# Microduino-Core_BLE.net
KiCad netlist of a schematic drawn in EAGLE
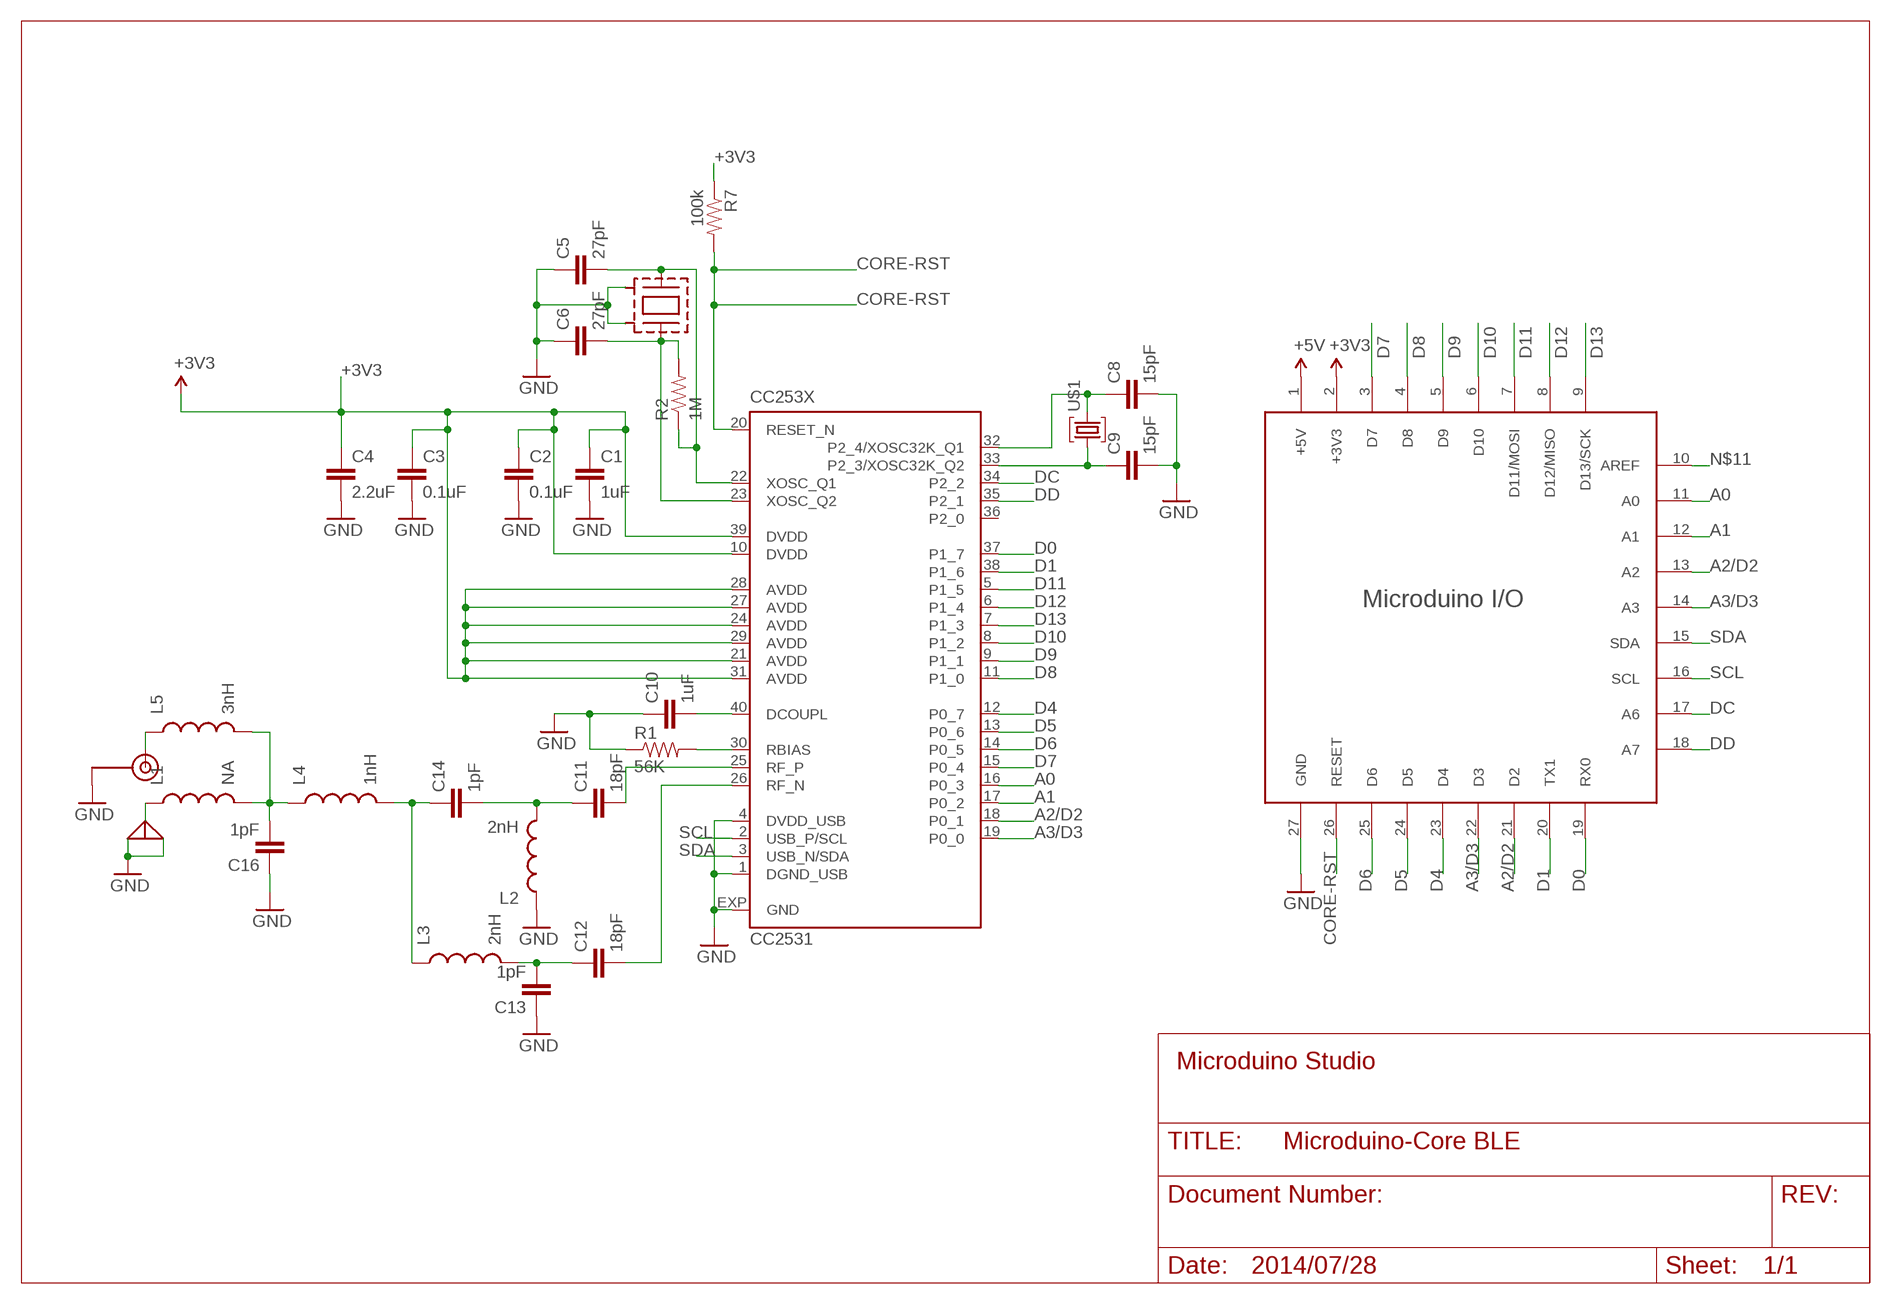
[diagram p0: schematic, sheet 1]

(export (version "E")
  (design (tool "Eeschema 10.0.6"))
  (components
    (comp (ref "C1")
      (value "1uF")
      (footprint "eagle-import:0603-CAP")
      (libsource (lib "eagle-import") (part "CAP0603-CAP"))
    )
    (comp (ref "C2")
      (value "0.1uF")
      (footprint "eagle-import:0402-CAP")
      (libsource (lib "eagle-import") (part "CAP0402-CAP"))
    )
    (comp (ref "C3")
      (value "0.1uF")
      (footprint "eagle-import:0402-CAP")
      (libsource (lib "eagle-import") (part "CAP0402-CAP"))
    )
    (comp (ref "C4")
      (value "2.2uF")
      (footprint "eagle-import:0402-CAP")
      (libsource (lib "eagle-import") (part "CAP0402-CAP"))
    )
    (comp (ref "C5")
      (value "27pF")
      (footprint "eagle-import:0402-CAP")
      (libsource (lib "eagle-import") (part "CAP0402-CAP"))
    )
    (comp (ref "C6")
      (value "27pF")
      (footprint "eagle-import:0402-CAP")
      (libsource (lib "eagle-import") (part "CAP0402-CAP"))
    )
    (comp (ref "C8")
      (value "15pF")
      (footprint "eagle-import:0402-CAP")
      (libsource (lib "eagle-import") (part "CAP0402-CAP"))
    )
    (comp (ref "C9")
      (value "15pF")
      (footprint "eagle-import:0402-CAP")
      (libsource (lib "eagle-import") (part "CAP0402-CAP"))
    )
    (comp (ref "C10")
      (value "1uF")
      (footprint "eagle-import:0603-CAP")
      (libsource (lib "eagle-import") (part "CAP0603-CAP"))
    )
    (comp (ref "C11")
      (value "18pF")
      (footprint "eagle-import:0402-CAP")
      (libsource (lib "eagle-import") (part "CAP0402-CAP"))
    )
    (comp (ref "C12")
      (value "18pF")
      (footprint "eagle-import:0402-CAP")
      (libsource (lib "eagle-import") (part "CAP0402-CAP"))
    )
    (comp (ref "C13")
      (value "1pF")
      (footprint "eagle-import:0402-CAP")
      (libsource (lib "eagle-import") (part "CAP0402-CAP"))
    )
    (comp (ref "C14")
      (value "1pF")
      (footprint "eagle-import:0402-CAP")
      (libsource (lib "eagle-import") (part "CAP0402-CAP"))
    )
    (comp (ref "C16")
      (value "1pF")
      (footprint "eagle-import:0402-CAP")
      (libsource (lib "eagle-import") (part "CAP0402-CAP"))
    )
    (comp (ref "CC253X")
      (value "CC2531")
      (footprint "eagle-import:RHA_S-PVQFN-N40")
      (fields (field (name "MPN") "CC2531F256RHAT"))
      (libsource (lib "eagle-import") (part "CC2531"))
    )
    (comp (ref "CRYS.1")
      (value "CRYSTAL-SMD")
      (footprint "eagle-import:CRYSTAL-SMD-3225")
      (libsource (lib "eagle-import") (part "CRYSTAL-SMD"))
    )
    (comp (ref "L1")
      (value "NA")
      (footprint "eagle-import:C0402")
      (libsource (lib "eagle-import") (part "INDUCTOR0402"))
    )
    (comp (ref "L2")
      (value "2nH")
      (footprint "eagle-import:C0402")
      (libsource (lib "eagle-import") (part "INDUCTOR0402"))
    )
    (comp (ref "L3")
      (value "2nH")
      (footprint "eagle-import:C0402")
      (libsource (lib "eagle-import") (part "INDUCTOR0402"))
    )
    (comp (ref "L4")
      (value "1nH")
      (footprint "eagle-import:C0402")
      (libsource (lib "eagle-import") (part "INDUCTOR0402"))
    )
    (comp (ref "L5")
      (value "3nH")
      (footprint "eagle-import:C0402")
      (libsource (lib "eagle-import") (part "INDUCTOR0402"))
    )
    (comp (ref "R1")
      (value "56K")
      (footprint "eagle-import:0402-RES")
      (libsource (lib "eagle-import") (part "RESISTOR0402-RES"))
    )
    (comp (ref "R2")
      (value "1M")
      (footprint "eagle-import:0402-RES")
      (libsource (lib "eagle-import") (part "RESISTOR0402-RES"))
    )
    (comp (ref "R7")
      (value "100k")
      (footprint "eagle-import:0402-RES")
      (libsource (lib "eagle-import") (part "RESISTOR0402-RES"))
    )
    (comp (ref "U$1")
      (value "32.768-3215")
      (footprint "eagle-import:3215-2PIN")
      (libsource (lib "eagle-import") (part "32.768-3215"))
    )
    (comp (ref "U$2")
      (value "ANT-2.4G")
      (footprint "eagle-import:ANT2.4G")
      (libsource (lib "eagle-import") (part "ANT-2.4G"))
    )
    (comp (ref "U$3")
      (value "ANT-IPEX")
      (footprint "eagle-import:IPEX")
      (libsource (lib "eagle-import") (part "ANT-IPEX"))
    )
    (comp (ref "U$7")
      (value "MICRDUINO-PINNORMAL")
      (footprint "eagle-import:27UPIN-NORMAL")
      (libsource (lib "eagle-import") (part "MICRDUINO-PINNORMAL"))
    )
  )
  (nets
    (net (code "1") (name "+3V3") (class "Default")
      (node (ref "C1") (pin "1") (pinfunction "1_1") (pintype "passive"))
      (node (ref "C2") (pin "1") (pinfunction "1_1") (pintype "passive"))
      (node (ref "C3") (pin "1") (pinfunction "1_1") (pintype "passive"))
      (node (ref "C4") (pin "1") (pinfunction "1_1") (pintype "passive"))
      (node (ref "CC253X") (pin "10") (pinfunction "DVDD_10") (pintype "power_in"))
      (node (ref "CC253X") (pin "21") (pinfunction "AVDD_21") (pintype "power_in"))
      (node (ref "CC253X") (pin "24") (pinfunction "AVDD_24") (pintype "power_in"))
      (node (ref "CC253X") (pin "27") (pinfunction "AVDD_27") (pintype "power_in"))
      (node (ref "CC253X") (pin "28") (pinfunction "AVDD_28") (pintype "power_in"))
      (node (ref "CC253X") (pin "29") (pinfunction "AVDD_29") (pintype "power_in"))
      (node (ref "CC253X") (pin "31") (pinfunction "AVDD_31") (pintype "power_in"))
      (node (ref "CC253X") (pin "39") (pinfunction "DVDD_39") (pintype "power_in"))
      (node (ref "R7") (pin "1") (pinfunction "1_1") (pintype "passive"))
      (node (ref "U$7") (pin "2") (pinfunction "+3V3_2") (pintype "bidirectional"))
    )
    (net (code "2") (name "+5V") (class "Default")
      (node (ref "U$7") (pin "1") (pinfunction "+5V_1") (pintype "bidirectional"))
    )
    (net (code "3") (name "/A0") (class "Default")
      (node (ref "CC253X") (pin "16") (pinfunction "P0_3_16") (pintype "bidirectional"))
      (node (ref "U$7") (pin "11") (pinfunction "A0_11") (pintype "bidirectional"))
    )
    (net (code "4") (name "/A1") (class "Default")
      (node (ref "CC253X") (pin "17") (pinfunction "P0_2_17") (pintype "bidirectional"))
      (node (ref "U$7") (pin "12") (pinfunction "A1_12") (pintype "bidirectional"))
    )
    (net (code "5") (name "/A2{slash}D2") (class "Default")
      (node (ref "CC253X") (pin "18") (pinfunction "P0_1_18") (pintype "bidirectional"))
      (node (ref "U$7") (pin "13") (pinfunction "A2_13") (pintype "bidirectional"))
      (node (ref "U$7") (pin "21") (pinfunction "D2_21") (pintype "bidirectional"))
    )
    (net (code "6") (name "/A3{slash}D3") (class "Default")
      (node (ref "CC253X") (pin "19") (pinfunction "P0_0_19") (pintype "bidirectional"))
      (node (ref "U$7") (pin "14") (pinfunction "A3_14") (pintype "bidirectional"))
      (node (ref "U$7") (pin "22") (pinfunction "D3_22") (pintype "bidirectional"))
    )
    (net (code "7") (name "/CORE-RST") (class "Default")
      (node (ref "CC253X") (pin "20") (pinfunction "RESET_N_20") (pintype "input"))
      (node (ref "R7") (pin "2") (pinfunction "2_2") (pintype "passive"))
      (node (ref "U$7") (pin "26") (pinfunction "RESET_26") (pintype "bidirectional"))
    )
    (net (code "8") (name "/D0") (class "Default")
      (node (ref "CC253X") (pin "37") (pinfunction "P1_7_37") (pintype "bidirectional"))
      (node (ref "U$7") (pin "19") (pinfunction "RX0_19") (pintype "bidirectional"))
    )
    (net (code "9") (name "/D1") (class "Default")
      (node (ref "CC253X") (pin "38") (pinfunction "P1_6_38") (pintype "bidirectional"))
      (node (ref "U$7") (pin "20") (pinfunction "TX1_20") (pintype "bidirectional"))
    )
    (net (code "10") (name "/D4") (class "Default")
      (node (ref "CC253X") (pin "12") (pinfunction "P0_7_12") (pintype "bidirectional"))
      (node (ref "U$7") (pin "23") (pinfunction "D4_23") (pintype "bidirectional"))
    )
    (net (code "11") (name "/D5") (class "Default")
      (node (ref "CC253X") (pin "13") (pinfunction "P0_6_13") (pintype "bidirectional"))
      (node (ref "U$7") (pin "24") (pinfunction "D5_24") (pintype "bidirectional"))
    )
    (net (code "12") (name "/D6") (class "Default")
      (node (ref "CC253X") (pin "14") (pinfunction "P0_5_14") (pintype "bidirectional"))
      (node (ref "U$7") (pin "25") (pinfunction "D6_25") (pintype "bidirectional"))
    )
    (net (code "13") (name "/D7") (class "Default")
      (node (ref "CC253X") (pin "15") (pinfunction "P0_4_15") (pintype "bidirectional"))
      (node (ref "U$7") (pin "3") (pinfunction "D7_3") (pintype "bidirectional"))
    )
    (net (code "14") (name "/D8") (class "Default")
      (node (ref "CC253X") (pin "11") (pinfunction "P1_0_11") (pintype "bidirectional"))
      (node (ref "U$7") (pin "4") (pinfunction "D8_4") (pintype "bidirectional"))
    )
    (net (code "15") (name "/D9") (class "Default")
      (node (ref "CC253X") (pin "9") (pinfunction "P1_1_9") (pintype "bidirectional"))
      (node (ref "U$7") (pin "5") (pinfunction "D9_5") (pintype "bidirectional"))
    )
    (net (code "16") (name "/D10") (class "Default")
      (node (ref "CC253X") (pin "8") (pinfunction "P1_2_8") (pintype "bidirectional"))
      (node (ref "U$7") (pin "6") (pinfunction "D10_6") (pintype "bidirectional"))
    )
    (net (code "17") (name "/D11") (class "Default")
      (node (ref "CC253X") (pin "5") (pinfunction "P1_5_5") (pintype "bidirectional"))
      (node (ref "U$7") (pin "7") (pinfunction "D11/MOSI_7") (pintype "bidirectional"))
    )
    (net (code "18") (name "/D12") (class "Default")
      (node (ref "CC253X") (pin "6") (pinfunction "P1_4_6") (pintype "bidirectional"))
      (node (ref "U$7") (pin "8") (pinfunction "D12/MISO_8") (pintype "bidirectional"))
    )
    (net (code "19") (name "/D13") (class "Default")
      (node (ref "CC253X") (pin "7") (pinfunction "P1_3_7") (pintype "bidirectional"))
      (node (ref "U$7") (pin "9") (pinfunction "D13/SCK_9") (pintype "bidirectional"))
    )
    (net (code "20") (name "/DC") (class "Default")
      (node (ref "CC253X") (pin "34") (pinfunction "P2_2_34") (pintype "bidirectional"))
      (node (ref "U$7") (pin "17") (pinfunction "A6_17") (pintype "bidirectional"))
    )
    (net (code "21") (name "/DD") (class "Default")
      (node (ref "CC253X") (pin "35") (pinfunction "P2_1_35") (pintype "bidirectional"))
      (node (ref "U$7") (pin "18") (pinfunction "A7_18") (pintype "bidirectional"))
    )
    (net (code "22") (name "/N$11") (class "Default")
      (node (ref "U$7") (pin "10") (pinfunction "AREF_10") (pintype "bidirectional"))
    )
    (net (code "23") (name "/SCL") (class "Default")
      (node (ref "CC253X") (pin "2") (pinfunction "USB_P/SCL_2") (pintype "bidirectional"))
      (node (ref "U$7") (pin "16") (pinfunction "SCL_16") (pintype "bidirectional"))
    )
    (net (code "24") (name "/SDA") (class "Default")
      (node (ref "CC253X") (pin "3") (pinfunction "USB_N/SDA_3") (pintype "bidirectional"))
      (node (ref "U$7") (pin "15") (pinfunction "SDA_15") (pintype "bidirectional"))
    )
    (net (code "25") (name "GND") (class "Default")
      (node (ref "C1") (pin "2") (pinfunction "2_2") (pintype "passive"))
      (node (ref "C10") (pin "1") (pinfunction "1_1") (pintype "passive"))
      (node (ref "C13") (pin "1") (pinfunction "1_1") (pintype "passive"))
      (node (ref "C16") (pin "1") (pinfunction "1_1") (pintype "passive"))
      (node (ref "C2") (pin "2") (pinfunction "2_2") (pintype "passive"))
      (node (ref "C3") (pin "2") (pinfunction "2_2") (pintype "passive"))
      (node (ref "C4") (pin "2") (pinfunction "2_2") (pintype "passive"))
      (node (ref "C5") (pin "1") (pinfunction "1_1") (pintype "passive"))
      (node (ref "C6") (pin "1") (pinfunction "1_1") (pintype "passive"))
      (node (ref "C8") (pin "2") (pinfunction "2_2") (pintype "passive"))
      (node (ref "C9") (pin "2") (pinfunction "2_2") (pintype "passive"))
      (node (ref "CC253X") (pin "1") (pinfunction "DGND_USB_1") (pintype "power_in"))
      (node (ref "CC253X") (pin "4") (pinfunction "DVDD_USB_4") (pintype "power_in"))
      (node (ref "CC253X") (pin "EXP") (pinfunction "GND_EXP") (pintype "passive"))
      (node (ref "CRYS.1") (pin "2") (pinfunction "2_2") (pintype "bidirectional"))
      (node (ref "CRYS.1") (pin "4") (pinfunction "4_4") (pintype "bidirectional"))
      (node (ref "L2") (pin "1") (pinfunction "1_1") (pintype "passive"))
      (node (ref "R1") (pin "1") (pinfunction "1_1") (pintype "passive"))
      (node (ref "U$2") (pin "GND") (pinfunction "GND2_GND") (pintype "bidirectional"))
      (node (ref "U$3") (pin "1") (pinfunction "GND1_1") (pintype "bidirectional"))
      (node (ref "U$3") (pin "2") (pinfunction "GND2_2") (pintype "bidirectional"))
      (node (ref "U$7") (pin "27") (pinfunction "GND_27") (pintype "bidirectional"))
    )
    (net (code "26") (name "Net-(C11-Pad1)") (class "Default")
      (node (ref "C11") (pin "1") (pinfunction "1_1") (pintype "passive"))
      (node (ref "C14") (pin "2") (pinfunction "2_2") (pintype "passive"))
      (node (ref "L2") (pin "2") (pinfunction "2_2") (pintype "passive"))
    )
    (net (code "27") (name "Net-(C12-Pad1)") (class "Default")
      (node (ref "C12") (pin "1") (pinfunction "1_1") (pintype "passive"))
      (node (ref "C13") (pin "2") (pinfunction "2_2") (pintype "passive"))
      (node (ref "L3") (pin "2") (pinfunction "2_2") (pintype "passive"))
    )
    (net (code "28") (name "Net-(C14-Pad1)") (class "Default")
      (node (ref "C14") (pin "1") (pinfunction "1_1") (pintype "passive"))
      (node (ref "L3") (pin "1") (pinfunction "1_1") (pintype "passive"))
      (node (ref "L4") (pin "2") (pinfunction "2_2") (pintype "passive"))
    )
    (net (code "29") (name "Net-(C16-Pad2)") (class "Default")
      (node (ref "C16") (pin "2") (pinfunction "2_2") (pintype "passive"))
      (node (ref "L1") (pin "2") (pinfunction "2_2") (pintype "passive"))
      (node (ref "L4") (pin "1") (pinfunction "1_1") (pintype "passive"))
      (node (ref "L5") (pin "2") (pinfunction "2_2") (pintype "passive"))
    )
    (net (code "30") (name "Net-(CC253X-DCOUPL)") (class "Default")
      (node (ref "C10") (pin "2") (pinfunction "2_2") (pintype "passive"))
      (node (ref "CC253X") (pin "40") (pinfunction "DCOUPL_40") (pintype "power_in"))
    )
    (net (code "31") (name "Net-(CC253X-P2_3{slash}XOSC32K_Q2)") (class "Default")
      (node (ref "C9") (pin "1") (pinfunction "1_1") (pintype "passive"))
      (node (ref "CC253X") (pin "33") (pinfunction "P2_3/XOSC32K_Q2_33") (pintype "bidirectional"))
      (node (ref "U$1") (pin "P$1") (pinfunction "1_P$1") (pintype "passive"))
    )
    (net (code "32") (name "Net-(CC253X-P2_4{slash}XOSC32K_Q1)") (class "Default")
      (node (ref "C8") (pin "1") (pinfunction "1_1") (pintype "passive"))
      (node (ref "CC253X") (pin "32") (pinfunction "P2_4/XOSC32K_Q1_32") (pintype "bidirectional"))
      (node (ref "U$1") (pin "P$2") (pinfunction "3_P$2") (pintype "passive"))
    )
    (net (code "33") (name "Net-(CC253X-RBIAS)") (class "Default")
      (node (ref "CC253X") (pin "30") (pinfunction "RBIAS_30") (pintype "bidirectional"))
      (node (ref "R1") (pin "2") (pinfunction "2_2") (pintype "passive"))
    )
    (net (code "34") (name "Net-(CC253X-RF_N)") (class "Default")
      (node (ref "C12") (pin "2") (pinfunction "2_2") (pintype "passive"))
      (node (ref "CC253X") (pin "26") (pinfunction "RF_N_26") (pintype "bidirectional"))
    )
    (net (code "35") (name "Net-(CC253X-RF_P)") (class "Default")
      (node (ref "C11") (pin "2") (pinfunction "2_2") (pintype "passive"))
      (node (ref "CC253X") (pin "25") (pinfunction "RF_P_25") (pintype "bidirectional"))
    )
    (net (code "36") (name "Net-(CC253X-XOSC_Q1)") (class "Default")
      (node (ref "C5") (pin "2") (pinfunction "2_2") (pintype "passive"))
      (node (ref "CC253X") (pin "22") (pinfunction "XOSC_Q1_22") (pintype "bidirectional"))
      (node (ref "CRYS.1") (pin "1") (pinfunction "1_1") (pintype "bidirectional"))
      (node (ref "R2") (pin "1") (pinfunction "1_1") (pintype "passive"))
    )
    (net (code "37") (name "Net-(CC253X-XOSC_Q2)") (class "Default")
      (node (ref "C6") (pin "2") (pinfunction "2_2") (pintype "passive"))
      (node (ref "CC253X") (pin "23") (pinfunction "XOSC_Q2_23") (pintype "bidirectional"))
      (node (ref "CRYS.1") (pin "3") (pinfunction "3_3") (pintype "bidirectional"))
      (node (ref "R2") (pin "2") (pinfunction "2_2") (pintype "passive"))
    )
    (net (code "38") (name "Net-(U$2-IN)") (class "Default")
      (node (ref "L5") (pin "1") (pinfunction "1_1") (pintype "passive"))
      (node (ref "U$2") (pin "ANT") (pinfunction "IN_ANT") (pintype "bidirectional"))
    )
    (net (code "39") (name "Net-(U$3-ANT)") (class "Default")
      (node (ref "L1") (pin "1") (pinfunction "1_1") (pintype "passive"))
      (node (ref "U$3") (pin "3") (pinfunction "ANT_3") (pintype "bidirectional"))
    )
    (net (code "40") (name "unconnected-(CC253X-P2_0-Pad36)") (class "Default")
      (node (ref "CC253X") (pin "36") (pinfunction "P2_0_36") (pintype "bidirectional"))
    )
  )
)
